# JacdacLightLevel_55.net
KiCad netlist of a schematic drawn in Altium Designer
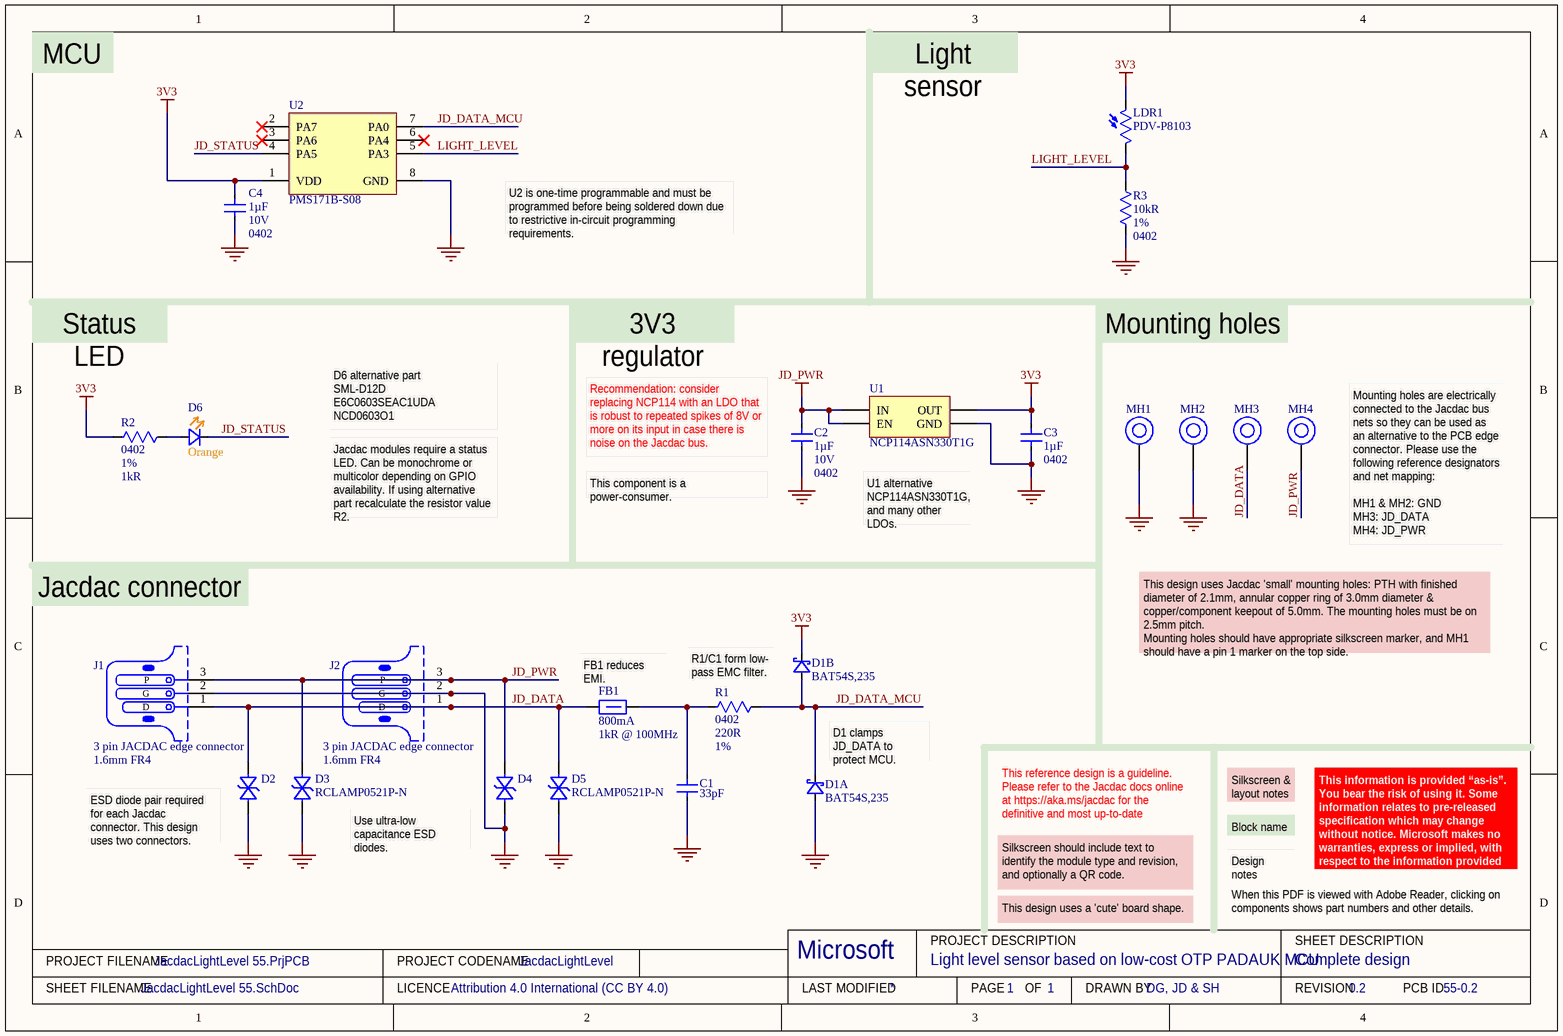
[diagram p0: JacdacLightLevel 55.SchDoc]

(export (version "E")
  (design (tool "Eeschema 10.0.6"))
  (components
    (comp (ref "C1")
      (value "CL05C330JB5NNNC")
      (footprint "C0402_0.55MM - without outline")
      (description "CAP CER 33PF 50V C0G/NP0 0402")
      (fields
        (field (name "MANUFACTURER") "Samsung")
        (field (name "TOLERANCE") "5%")
        (field (name "CAPACITANCE") "33pF")
      )
      (libsource (lib "Samsung") (part "CL05C330JB5NNNC"))
    )
    (comp (ref "C2")
      (value "CL05A105KP5NNNC")
      (footprint "C0402_0.55MM - without outline")
      (description "CAP CER 1UF 10V X5R 0402")
      (fields
        (field (name "MANUFACTURER") "Samsung")
        (field (name "TOLERANCE") "10%")
        (field (name "CAPACITANCE") "1µF")
        (field (name "VOLTAGE RATING") "10V")
        (field (name "CASE CODE (IMPERIAL)") "0402")
        (field (name "CREATED") "DG")
        (field (name "CHECKED") "?")
      )
      (libsource (lib "Samsung") (part "CL05A105KP5NNNC"))
    )
    (comp (ref "C3")
      (value "CL05A105KP5NNNC")
      (footprint "C0402_0.55MM - without outline")
      (description "CAP CER 1UF 10V X5R 0402")
      (fields
        (field (name "MANUFACTURER") "Samsung")
        (field (name "TOLERANCE") "10%")
        (field (name "CAPACITANCE") "1µF")
        (field (name "CASE CODE (IMPERIAL)") "0402")
        (field (name "CREATED") "DG")
        (field (name "CHECKED") "?")
      )
      (libsource (lib "Samsung") (part "CL05A105KP5NNNC"))
    )
    (comp (ref "C4")
      (value "CL05A105KP5NNNC")
      (footprint "C0402_0.55MM - without outline")
      (description "CAP CER 1UF 10V X5R 0402")
      (fields
        (field (name "MANUFACTURER") "Samsung")
        (field (name "TOLERANCE") "10%")
        (field (name "CAPACITANCE") "1µF")
        (field (name "VOLTAGE RATING") "10V")
        (field (name "CASE CODE (IMPERIAL)") "0402")
        (field (name "CREATED") "DG")
        (field (name "CHECKED") "?")
      )
      (libsource (lib "Samsung") (part "CL05A105KP5NNNC"))
    )
    (comp (ref "D1")
      (value "BAT54S")
      (footprint "NXP-BAT54S-TO-236AB - without outline")
      (description "DIODE ARRAY SCHOTTKY 30V SOT23")
      (fields (field (name "MANUFACTURER") "Nexperia") (field (name "MANUFACTURER PART NUMBER") "BAT54S,235"))
      (libsource (lib "NXP") (part "BAT54S"))
    )
    (comp (ref "D2")
      (value "RCLAMP0521P-N")
      (footprint "TVS 0402 - L")
      (description "Bidirectional 5V (Max) 6V 16V 3.5A (8/20us) 0402 TVS RoHS")
      (fields
        (field (name "MANUFACTURER") "Born Semiconductor")
        (field (name "CREATED BY") "D Gakure")
        (field (name "CHECKED BY") "?")
      )
      (libsource (lib "BornSemiconductor") (part "RCLAMP0521P-N"))
    )
    (comp (ref "D3")
      (value "RCLAMP0521P-N")
      (footprint "TVS 0402 - L")
      (description "Bidirectional 5V (Max) 6V 16V 3.5A (8/20us) 0402 TVS RoHS")
      (fields
        (field (name "MANUFACTURER") "Born Semiconductor")
        (field (name "MANUFACTURER PART NUMBER") "RCLAMP0521P-N")
        (field (name "CREATED BY") "D Gakure")
        (field (name "CHECKED BY") "?")
      )
      (libsource (lib "BornSemiconductor") (part "RCLAMP0521P-N"))
    )
    (comp (ref "D4")
      (value "RCLAMP0521P-N")
      (footprint "TVS 0402 - L")
      (description "Bidirectional 5V (Max) 6V 16V 3.5A (8/20us) 0402 TVS RoHS")
      (fields
        (field (name "MANUFACTURER") "Born Semiconductor")
        (field (name "CREATED BY") "D Gakure")
        (field (name "CHECKED BY") "?")
      )
      (libsource (lib "BornSemiconductor") (part "RCLAMP0521P-N"))
    )
    (comp (ref "D5")
      (value "RCLAMP0521P-N")
      (footprint "TVS 0402 - L")
      (description "Bidirectional 5V (Max) 6V 16V 3.5A (8/20us) 0402 TVS RoHS")
      (fields
        (field (name "MANUFACTURER") "Born Semiconductor")
        (field (name "MANUFACTURER PART NUMBER") "RCLAMP0521P-N")
        (field (name "CREATED BY") "D Gakure")
        (field (name "CHECKED BY") "?")
      )
      (libsource (lib "BornSemiconductor") (part "RCLAMP0521P-N"))
    )
    (comp (ref "D6")
      (value "~")
      (footprint "0603 Orange - without outline")
      (description "LED ORANGE DIFFUSED 1608 SMD")
      (fields
        (field (name "MANUFACTURER") "Everlight Elec")
        (field (name "MANUFACTURER PART NUMBER") "19-217/S2C-AQ1R1B/3T")
        (field (name "COLOUR") "Orange")
      )
      (libsource (lib "EverlightElec") (part "19-217/S2C-AQ1R1B/3T"))
    )
    (comp (ref "FB1")
      (value "TDK MPZ1608S102ATA00")
      (footprint "TDK MPZ1608 0.8mm - without outline")
      (description "0603 1k@100MHz 0.8A chip")
      (fields
        (field (name "TOLERANCE") "25%")
        (field (name "MANUFACTURER") "TDK")
        (field (name "CURRENT RATING") "800mA")
        (field (name "IMPEDANCE") "1kR @ 100MHz")
      )
      (libsource (lib "TDK") (part "TDK MPZ1608S102ATA00"))
    )
    (comp (ref "J1")
      (value "3 pin JACDAC edge connector")
      (footprint "JACDAC_EDGE_CONNECTOR_NO_TRACES")
      (description "3 pin Jacdac edge connector 1.27mm pitch")
      (fields
        (field (name "MANUFACTURER PART NUMBER") "JACDAC_EDGE_CONNECTOR")
        (field (name "PCB TYPE") "1.6mm FR4")
        (field (name "CHECKED BY") "?")
        (field (name "CREATED BY") "D. Gakure")
      )
      (libsource (lib "generic-con") (part "Jacdac edge connector"))
    )
    (comp (ref "J2")
      (value "3 pin JACDAC edge connector")
      (footprint "JACDAC_EDGE_CONNECTOR_NO_TRACES")
      (description "3 pin Jacdac edge connector 1.27mm pitch")
      (fields
        (field (name "MANUFACTURER PART NUMBER") "JACDAC_EDGE_CONNECTOR")
        (field (name "PCB TYPE") "1.6mm FR4")
        (field (name "CHECKED BY") "?")
        (field (name "CREATED BY") "D. Gakure")
      )
      (libsource (lib "generic-con") (part "Jacdac edge connector"))
    )
    (comp (ref "LDR1")
      (value "PDV-P8103")
      (footprint "PDV-P8103")
      (description "PHOTOCELL 16-33KOHM")
      (fields
        (field (name "MANUFACTURER") "Advanced Photonix")
        (field (name "MANUFACTURER PART NUMBER") "PDV-P8103")
      )
      (libsource (lib "AdvancedPhotonix") (part "PDV-P8103"))
    )
    (comp (ref "MH1")
      (value "MH_5.0MMK_3.0MMC_2.1MMD_PTH")
      (footprint "MH_5.0MMK_3.0MMC_2.1MMD_PTH")
      (description "Mounting Hole 5.0mm keepout, 3.0mm annualar ring and 2.1mm Drill PTH")
      (libsource (lib "generic") (part "MH_5.0MMK_3.0MMC_2.1MMD_PTH"))
    )
    (comp (ref "MH2")
      (value "MH_5.0MMK_3.0MMC_2.1MMD_PTH")
      (footprint "MH_5.0MMK_3.0MMC_2.1MMD_PTH")
      (description "Mounting Hole 5.0mm keepout, 3.0mm annualar ring and 2.1mm Drill PTH")
      (libsource (lib "generic") (part "MH_5.0MMK_3.0MMC_2.1MMD_PTH"))
    )
    (comp (ref "MH3")
      (value "MH_5.0MMK_3.0MMC_2.1MMD_PTH")
      (footprint "MH_5.0MMK_3.0MMC_2.1MMD_PTH")
      (description "Mounting Hole 5.0mm keepout, 3.0mm annualar ring and 2.1mm Drill PTH")
      (libsource (lib "generic") (part "MH_5.0MMK_3.0MMC_2.1MMD_PTH"))
    )
    (comp (ref "MH4")
      (value "MH_5.0MMK_3.0MMC_2.1MMD_PTH")
      (footprint "MH_5.0MMK_3.0MMC_2.1MMD_PTH")
      (description "Mounting Hole 5.0mm keepout, 3.0mm annualar ring and 2.1mm Drill PTH")
      (libsource (lib "generic") (part "MH_5.0MMK_3.0MMC_2.1MMD_PTH"))
    )
    (comp (ref "R1")
      (value "RC0402FR-07220RL")
      (footprint "R0402 - Without outline")
      (description "RES SMD 220 OHM 1% 1/16W 0402")
      (fields
        (field (name "MANUFACTURER") "Yageo")
        (field (name "CASE CODE (IMPERIAL)") "0402")
        (field (name "RESISTANCE") "220R")
        (field (name "TOLERANCE") "1%")
        (field (name "CREATED") "D.G")
        (field (name "CHECKED") "?")
      )
      (libsource (lib "Yageo") (part "RC0402FR-07220RL"))
    )
    (comp (ref "R2")
      (value "RC0402FR-071KL")
      (footprint "R0402 - Without outline")
      (description "RES SMD 1K OHM 1% 1/16W 0402")
      (fields
        (field (name "MANUFACTURER") "Yageo")
        (field (name "CASE CODE (IMPERIAL)") "0402")
        (field (name "TOLERANCE") "1%")
        (field (name "RESISTANCE") "1kR")
        (field (name "CREATED") "D.G")
        (field (name "CHECKED") "?")
      )
      (libsource (lib "Yageo") (part "RC0402FR-071KL"))
    )
    (comp (ref "R3")
      (value "10k")
      (footprint "R0402 - Without outline")
      (description "RES SMD 10K OHM 1% 1/16W 0402")
      (fields
        (field (name "MANUFACTURER") "Yageo")
        (field (name "MANUFACTURER PART NUMBER") "RC0402FR-0710KL")
        (field (name "RESISTANCE") "10kR")
        (field (name "TOLERANCE") "1%")
        (field (name "CASE CODE (IMPERIAL)") "0402")
        (field (name "CHECKED") "?")
        (field (name "CREATED") "DG")
      )
      (libsource (lib "Yageo") (part "RC0402FR-0710KL"))
    )
    (comp (ref "U1")
      (value "LDO 3.3V/300 mA")
      (footprint "ON_SEMI-SOT23-5 - without outline")
      (fields
        (field (name "MANUFACTURER") "ON Semiconductor")
        (field (name "MANUFACTURER PART NUMBER") "NCP114ASN330T1G")
        (field (name "CREATED") "DG")
        (field (name "CHECKED") "?")
      )
      (libsource (lib "OnSemiconductor") (part "NCP114ASN330T1G"))
    )
    (comp (ref "U2")
      (value "PMS171B-S08")
      (footprint "SOP-8")
      (description "8bit OTP MCU with 8-bit ADC")
      (fields (field (name "MANUFACTURER") "PADAUK") (field (name "MANUFACTURER PART NUMBER") "PMS171B-S08"))
      (libsource (lib "PADAUK") (part "PMS171B-S08"))
    )
  )
  (nets
    (net (code "1") (name "/JD_DATA") (class "Default")
      (node (ref "D2") (pin "1") (pinfunction "K_1") (pintype "passive"))
      (node (ref "D5") (pin "1") (pinfunction "K_1") (pintype "passive"))
      (node (ref "FB1") (pin "1") (pinfunction "1_1") (pintype "passive"))
      (node (ref "J1") (pin "1") (pinfunction "D_1") (pintype "passive"))
      (node (ref "J2") (pin "1") (pinfunction "D_1") (pintype "passive"))
      (node (ref "MH3") (pin "1") (pinfunction "1_1") (pintype "passive"))
    )
    (net (code "2") (name "/JD_DATA_MCU") (class "Default")
      (node (ref "D1") (pin "3") (pinfunction "K_3") (pintype "passive"))
      (node (ref "R1") (pin "1") (pinfunction "1_1") (pintype "passive"))
      (node (ref "U2") (pin "7") (pinfunction "PA0_7") (pintype "passive"))
    )
    (net (code "3") (name "/JD_STATUS") (class "Default")
      (node (ref "D6") (pin "1") (pinfunction "K_1") (pintype "passive"))
      (node (ref "U2") (pin "4") (pinfunction "PA5_4") (pintype "passive"))
    )
    (net (code "4") (name "/LIGHT_LEVEL") (class "Default")
      (node (ref "LDR1") (pin "2") (pinfunction "2_2") (pintype "passive"))
      (node (ref "R3") (pin "1") (pinfunction "1_1") (pintype "passive"))
      (node (ref "U2") (pin "5") (pinfunction "PA3_5") (pintype "passive"))
    )
    (net (code "5") (name "3V3") (class "Default")
      (node (ref "C3") (pin "2") (pinfunction "2_2") (pintype "passive"))
      (node (ref "C4") (pin "2") (pinfunction "2_2") (pintype "passive"))
      (node (ref "D1") (pin "2") (pinfunction "K_2") (pintype "passive"))
      (node (ref "LDR1") (pin "1") (pinfunction "1_1") (pintype "passive"))
      (node (ref "R2") (pin "2") (pinfunction "2_2") (pintype "passive"))
      (node (ref "U1") (pin "5") (pinfunction "OUT_5") (pintype "passive"))
      (node (ref "U2") (pin "1") (pinfunction "VDD_1") (pintype "passive"))
    )
    (net (code "6") (name "GND") (class "Default")
      (node (ref "C1") (pin "1") (pinfunction "1_1") (pintype "passive"))
      (node (ref "C2") (pin "1") (pinfunction "1_1") (pintype "passive"))
      (node (ref "C3") (pin "1") (pinfunction "1_1") (pintype "passive"))
      (node (ref "C4") (pin "1") (pinfunction "1_1") (pintype "passive"))
      (node (ref "D1") (pin "1") (pinfunction "A_1") (pintype "passive"))
      (node (ref "D2") (pin "2") (pinfunction "A_2") (pintype "passive"))
      (node (ref "D3") (pin "2") (pinfunction "A_2") (pintype "passive"))
      (node (ref "D4") (pin "2") (pinfunction "A_2") (pintype "passive"))
      (node (ref "D5") (pin "2") (pinfunction "A_2") (pintype "passive"))
      (node (ref "J1") (pin "2") (pinfunction "G_2") (pintype "passive"))
      (node (ref "J2") (pin "2") (pinfunction "G_2") (pintype "passive"))
      (node (ref "MH1") (pin "1") (pinfunction "1_1") (pintype "passive"))
      (node (ref "MH2") (pin "1") (pinfunction "1_1") (pintype "passive"))
      (node (ref "R3") (pin "2") (pinfunction "2_2") (pintype "passive"))
      (node (ref "U1") (pin "2") (pinfunction "GND_2") (pintype "passive"))
      (node (ref "U2") (pin "8") (pinfunction "GND_8") (pintype "passive"))
    )
    (net (code "7") (name "JD_PWR") (class "Default")
      (node (ref "C2") (pin "2") (pinfunction "2_2") (pintype "passive"))
      (node (ref "D3") (pin "1") (pinfunction "K_1") (pintype "passive"))
      (node (ref "D4") (pin "1") (pinfunction "K_1") (pintype "passive"))
      (node (ref "J1") (pin "3") (pinfunction "P_3") (pintype "passive"))
      (node (ref "J2") (pin "3") (pinfunction "P_3") (pintype "passive"))
      (node (ref "MH4") (pin "1") (pinfunction "1_1") (pintype "passive"))
      (node (ref "U1") (pin "1") (pinfunction "IN_1") (pintype "passive"))
      (node (ref "U1") (pin "3") (pinfunction "EN_3") (pintype "passive"))
    )
    (net (code "8") (name "Net-(C1-Pad2)") (class "Default")
      (node (ref "C1") (pin "2") (pinfunction "2_2") (pintype "passive"))
      (node (ref "FB1") (pin "2") (pinfunction "2_2") (pintype "passive"))
      (node (ref "R1") (pin "2") (pinfunction "2_2") (pintype "passive"))
    )
    (net (code "9") (name "Net-(D6-A)") (class "Default")
      (node (ref "D6") (pin "2") (pinfunction "A_2") (pintype "passive"))
      (node (ref "R2") (pin "1") (pinfunction "1_1") (pintype "passive"))
    )
    (net (code "10") (name "unconnected-(U2-PA4-Pad6)") (class "Default")
      (node (ref "U2") (pin "6") (pinfunction "PA4_6") (pintype "passive+no_connect"))
    )
    (net (code "11") (name "unconnected-(U2-PA6-Pad3)") (class "Default")
      (node (ref "U2") (pin "3") (pinfunction "PA6_3") (pintype "passive+no_connect"))
    )
    (net (code "12") (name "unconnected-(U2-PA7-Pad2)") (class "Default")
      (node (ref "U2") (pin "2") (pinfunction "PA7_2") (pintype "passive+no_connect"))
    )
  )
)
